# Arm_V2.net
KiCad netlist of a schematic drawn in Altium Designer
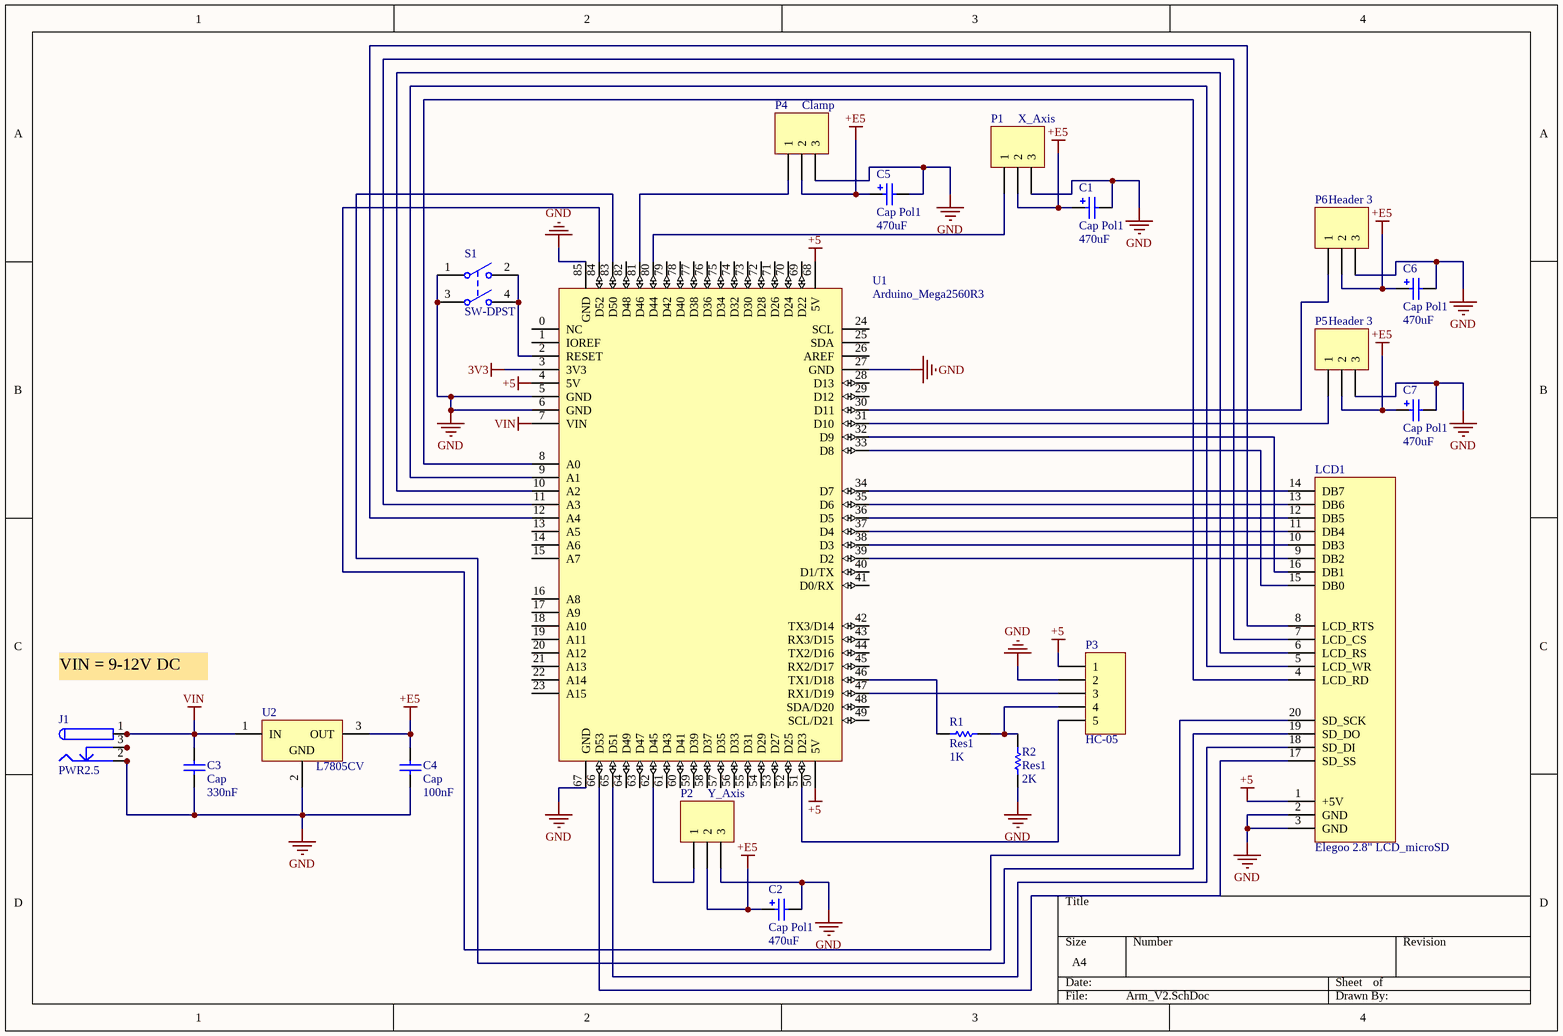
[diagram p0: Arm_V2.SchDoc]

(export (version "E")
  (design (tool "Eeschema 10.0.6"))
  (components
    (comp (ref "C1")
      (value "Cap Pol1")
      (footprint "PCAP_3")
      (description "Polarized Capacitor (Radial)")
      (fields (field (name "ALTIUM_VALUE") "470uF") (field (name "PUBLISHER") "Altium Limited"))
      (libsource (lib "Miscellaneous Devices") (part "Cap Pol1"))
    )
    (comp (ref "C2")
      (value "Cap Pol1")
      (footprint "PCAP_3")
      (description "Polarized Capacitor (Radial)")
      (fields (field (name "ALTIUM_VALUE") "470uF") (field (name "PUBLISHER") "Altium Limited"))
      (libsource (lib "Miscellaneous Devices") (part "Cap Pol1"))
    )
    (comp (ref "C3")
      (value "Cap")
      (footprint "RAD-0.2")
      (description "Capacitor")
      (fields (field (name "ALTIUM_VALUE") "330nF") (field (name "PUBLISHER") "Altium Limited"))
      (libsource (lib "Miscellaneous Devices") (part "Cap"))
    )
    (comp (ref "C4")
      (value "Cap")
      (footprint "RAD-0.2")
      (description "Capacitor")
      (fields (field (name "ALTIUM_VALUE") "100nF") (field (name "PUBLISHER") "Altium Limited"))
      (libsource (lib "Miscellaneous Devices") (part "Cap"))
    )
    (comp (ref "C5")
      (value "Cap Pol1")
      (footprint "PCAP_3")
      (description "Polarized Capacitor (Radial)")
      (fields (field (name "ALTIUM_VALUE") "470uF") (field (name "PUBLISHER") "Altium Limited"))
      (libsource (lib "Miscellaneous Devices") (part "Cap Pol1"))
    )
    (comp (ref "C6")
      (value "Cap Pol1")
      (footprint "PCAP_3")
      (description "Polarized Capacitor (Radial)")
      (fields (field (name "ALTIUM_VALUE") "470uF") (field (name "PUBLISHER") "Altium Limited"))
      (libsource (lib "Miscellaneous Devices") (part "Cap Pol1"))
    )
    (comp (ref "C7")
      (value "Cap Pol1")
      (footprint "PCAP_3")
      (description "Polarized Capacitor (Radial)")
      (fields (field (name "ALTIUM_VALUE") "470uF") (field (name "PUBLISHER") "Altium Limited"))
      (libsource (lib "Miscellaneous Devices") (part "Cap Pol1"))
    )
    (comp (ref "J1")
      (value "PWR2.5")
      (footprint "KLD-0202")
      (description "Low Voltage Power Supply Connector")
      (fields (field (name "PUBLISHER") "Altium Limited"))
      (libsource (lib "Miscellaneous Connectors") (part "PWR2.5"))
    )
    (comp (ref "LCD1")
      (value "Elegoo 2.8\" LCD_microSD")
      (footprint "Elegoo 2.8\" LCD w/h microSD")
      (libsource (lib "Miscellaneous Devices") (part "Elegoo 2.8{dblquote} LCD_microSD"))
    )
    (comp (ref "P1")
      (value "X_Axis")
      (footprint "HDR1X3")
      (description "Header, 3-Pin")
      (fields (field (name "PUBLISHER") "Altium Limited"))
      (libsource (lib "Miscellaneous Connectors") (part "Header 3"))
    )
    (comp (ref "P2")
      (value "Y_Axis")
      (footprint "HDR1X3")
      (description "Header, 3-Pin")
      (fields (field (name "PUBLISHER") "Altium Limited"))
      (libsource (lib "Miscellaneous Connectors") (part "Header 3"))
    )
    (comp (ref "P3")
      (value "HC-05")
      (footprint "HDR1X5H")
      (description "Header, 5-Pin, Right Angle")
      (fields (field (name "PUBLISHER") "Altium Limited"))
      (libsource (lib "Miscellaneous Connectors") (part "Header 5H"))
    )
    (comp (ref "P4")
      (value "Clamp")
      (footprint "HDR1X3")
      (description "Header, 3-Pin")
      (fields (field (name "PUBLISHER") "Altium Limited"))
      (libsource (lib "Miscellaneous Connectors") (part "Header 3"))
    )
    (comp (ref "P5")
      (value "Header 3")
      (footprint "HDR1X3")
      (description "Header, 3-Pin")
      (fields (field (name "PUBLISHER") "Altium Limited"))
      (libsource (lib "Miscellaneous Connectors") (part "Header 3"))
    )
    (comp (ref "P6")
      (value "Header 3")
      (footprint "HDR1X3")
      (description "Header, 3-Pin")
      (fields (field (name "PUBLISHER") "Altium Limited"))
      (libsource (lib "Miscellaneous Connectors") (part "Header 3"))
    )
    (comp (ref "R1")
      (value "Res1")
      (footprint "AXIAL-0.3")
      (description "Resistor")
      (fields (field (name "ALTIUM_VALUE") "1K") (field (name "PUBLISHER") "Altium Limited"))
      (libsource (lib "Miscellaneous Devices") (part "Res1"))
    )
    (comp (ref "R2")
      (value "Res1")
      (footprint "AXIAL-0.3")
      (description "Resistor")
      (fields (field (name "ALTIUM_VALUE") "2K") (field (name "PUBLISHER") "Altium Limited"))
      (libsource (lib "Miscellaneous Devices") (part "Res1"))
    )
    (comp (ref "S1")
      (value "SW-DPST")
      (footprint "DPST-4")
      (description "Double-Pole, Single-Throw Switch")
      (fields (field (name "PUBLISHER") "Altium Limited"))
      (libsource (lib "Miscellaneous Devices") (part "SW-DPST"))
    )
    (comp (ref "U1")
      (value "Arduino_Mega2560R3")
      (footprint "ARDUINO_MEGA2560R3")
      (libsource (lib "Miscellaneous Devices") (part "Arduino_Mega2560R3"))
    )
    (comp (ref "U2")
      (value "L7805CV")
      (footprint "TO220")
      (description "Positive Voltage Regulator, 5V, 3-Pin TO-220")
      (libsource (lib "STMicroelectronics Power Management Linear Regulator") (part "L7805CV"))
    )
  )
  (nets
    (net (code "1") (name "+5") (class "Default")
      (node (ref "LCD1") (pin "1") (pinfunction "+5V_1") (pintype "passive"))
      (node (ref "P3") (pin "1") (pinfunction "1_1") (pintype "passive"))
      (node (ref "U1") (pin "4") (pinfunction "5V_4") (pintype "power_in"))
      (node (ref "U1") (pin "50") (pinfunction "5V_50") (pintype "power_in"))
      (node (ref "U1") (pin "68") (pinfunction "5V_68") (pintype "power_in"))
    )
    (net (code "2") (name "+E5") (class "Default")
      (node (ref "C1") (pin "1") (pinfunction "1_1") (pintype "passive"))
      (node (ref "C2") (pin "1") (pinfunction "1_1") (pintype "passive"))
      (node (ref "C4") (pin "2") (pinfunction "2_2") (pintype "passive"))
      (node (ref "C5") (pin "1") (pinfunction "1_1") (pintype "passive"))
      (node (ref "C6") (pin "1") (pinfunction "1_1") (pintype "passive"))
      (node (ref "C7") (pin "1") (pinfunction "1_1") (pintype "passive"))
      (node (ref "P1") (pin "2") (pinfunction "2_2") (pintype "passive"))
      (node (ref "P2") (pin "2") (pinfunction "2_2") (pintype "passive"))
      (node (ref "P4") (pin "2") (pinfunction "2_2") (pintype "passive"))
      (node (ref "P5") (pin "2") (pinfunction "2_2") (pintype "passive"))
      (node (ref "P6") (pin "2") (pinfunction "2_2") (pintype "passive"))
      (node (ref "U2") (pin "3") (pinfunction "OUT_3") (pintype "power_in"))
    )
    (net (code "3") (name "3V3") (class "Default")
      (node (ref "U1") (pin "3") (pinfunction "3V3_3") (pintype "power_in"))
    )
    (net (code "4") (name "GND") (class "Default")
      (node (ref "C1") (pin "2") (pinfunction "2_2") (pintype "passive"))
      (node (ref "C2") (pin "2") (pinfunction "2_2") (pintype "passive"))
      (node (ref "C3") (pin "1") (pinfunction "1_1") (pintype "passive"))
      (node (ref "C4") (pin "1") (pinfunction "1_1") (pintype "passive"))
      (node (ref "C5") (pin "2") (pinfunction "2_2") (pintype "passive"))
      (node (ref "C6") (pin "2") (pinfunction "2_2") (pintype "passive"))
      (node (ref "C7") (pin "2") (pinfunction "2_2") (pintype "passive"))
      (node (ref "J1") (pin "2") (pinfunction "2_2") (pintype "power_in"))
      (node (ref "J1") (pin "2A") (pinfunction "2A_2A") (pintype "power_in"))
      (node (ref "J1") (pin "2B") (pinfunction "2B_2B") (pintype "power_in"))
      (node (ref "LCD1") (pin "2") (pinfunction "GND_2") (pintype "passive"))
      (node (ref "LCD1") (pin "3") (pinfunction "GND_3") (pintype "passive"))
      (node (ref "P1") (pin "3") (pinfunction "3_3") (pintype "passive"))
      (node (ref "P2") (pin "3") (pinfunction "3_3") (pintype "passive"))
      (node (ref "P3") (pin "2") (pinfunction "2_2") (pintype "passive"))
      (node (ref "P4") (pin "3") (pinfunction "3_3") (pintype "passive"))
      (node (ref "P5") (pin "3") (pinfunction "3_3") (pintype "passive"))
      (node (ref "P6") (pin "3") (pinfunction "3_3") (pintype "passive"))
      (node (ref "R2") (pin "1") (pinfunction "1_1") (pintype "passive"))
      (node (ref "S1") (pin "1") (pinfunction "COMMON1_1") (pintype "passive"))
      (node (ref "S1") (pin "3") (pinfunction "COMMON2_3") (pintype "passive"))
      (node (ref "U1") (pin "27") (pinfunction "GND_27") (pintype "power_in"))
      (node (ref "U1") (pin "5") (pinfunction "GND_5") (pintype "power_in"))
      (node (ref "U1") (pin "6") (pinfunction "GND_6") (pintype "power_in"))
      (node (ref "U1") (pin "67") (pinfunction "GND_67") (pintype "power_in"))
      (node (ref "U1") (pin "85") (pinfunction "GND_85") (pintype "power_in"))
      (node (ref "U2") (pin "2") (pinfunction "GND_2") (pintype "power_in"))
    )
    (net (code "5") (name "Net-(J1-Pad3)") (class "Default")
      (node (ref "J1") (pin "3") (pinfunction "3_3") (pintype "power_in"))
      (node (ref "J1") (pin "3A") (pinfunction "3A_3A") (pintype "power_in"))
      (node (ref "J1") (pin "3B") (pinfunction "3B_3B") (pintype "power_in"))
    )
    (net (code "6") (name "Net-(LCD1-DB0)") (class "Default")
      (node (ref "LCD1") (pin "15") (pinfunction "DB0_15") (pintype "passive"))
      (node (ref "U1") (pin "33") (pinfunction "D8_33") (pintype "bidirectional"))
    )
    (net (code "7") (name "Net-(LCD1-DB1)") (class "Default")
      (node (ref "LCD1") (pin "16") (pinfunction "DB1_16") (pintype "passive"))
      (node (ref "U1") (pin "32") (pinfunction "D9_32") (pintype "bidirectional"))
    )
    (net (code "8") (name "Net-(LCD1-DB2)") (class "Default")
      (node (ref "LCD1") (pin "9") (pinfunction "DB2_9") (pintype "passive"))
      (node (ref "U1") (pin "39") (pinfunction "D2_39") (pintype "bidirectional"))
    )
    (net (code "9") (name "Net-(LCD1-DB3)") (class "Default")
      (node (ref "LCD1") (pin "10") (pinfunction "DB3_10") (pintype "passive"))
      (node (ref "U1") (pin "38") (pinfunction "D3_38") (pintype "bidirectional"))
    )
    (net (code "10") (name "Net-(LCD1-DB4)") (class "Default")
      (node (ref "LCD1") (pin "11") (pinfunction "DB4_11") (pintype "passive"))
      (node (ref "U1") (pin "37") (pinfunction "D4_37") (pintype "bidirectional"))
    )
    (net (code "11") (name "Net-(LCD1-DB5)") (class "Default")
      (node (ref "LCD1") (pin "12") (pinfunction "DB5_12") (pintype "passive"))
      (node (ref "U1") (pin "36") (pinfunction "D5_36") (pintype "bidirectional"))
    )
    (net (code "12") (name "Net-(LCD1-DB6)") (class "Default")
      (node (ref "LCD1") (pin "13") (pinfunction "DB6_13") (pintype "passive"))
      (node (ref "U1") (pin "35") (pinfunction "D6_35") (pintype "bidirectional"))
    )
    (net (code "13") (name "Net-(LCD1-DB7)") (class "Default")
      (node (ref "LCD1") (pin "14") (pinfunction "DB7_14") (pintype "passive"))
      (node (ref "U1") (pin "34") (pinfunction "D7_34") (pintype "bidirectional"))
    )
    (net (code "14") (name "Net-(LCD1-LCD_CS)") (class "Default")
      (node (ref "LCD1") (pin "7") (pinfunction "LCD_CS_7") (pintype "passive"))
      (node (ref "U1") (pin "11") (pinfunction "A3_11") (pintype "passive"))
    )
    (net (code "15") (name "Net-(LCD1-LCD_RD)") (class "Default")
      (node (ref "LCD1") (pin "4") (pinfunction "LCD_RD_4") (pintype "passive"))
      (node (ref "U1") (pin "8") (pinfunction "A0_8") (pintype "passive"))
    )
    (net (code "16") (name "Net-(LCD1-LCD_RS)") (class "Default")
      (node (ref "LCD1") (pin "6") (pinfunction "LCD_RS_6") (pintype "passive"))
      (node (ref "U1") (pin "10") (pinfunction "A2_10") (pintype "passive"))
    )
    (net (code "17") (name "Net-(LCD1-LCD_RTS)") (class "Default")
      (node (ref "LCD1") (pin "8") (pinfunction "LCD_RTS_8") (pintype "passive"))
      (node (ref "U1") (pin "12") (pinfunction "A4_12") (pintype "passive"))
    )
    (net (code "18") (name "Net-(LCD1-LCD_WR)") (class "Default")
      (node (ref "LCD1") (pin "5") (pinfunction "LCD_WR_5") (pintype "passive"))
      (node (ref "U1") (pin "9") (pinfunction "A1_9") (pintype "passive"))
    )
    (net (code "19") (name "Net-(LCD1-SD_DI)") (class "Default")
      (node (ref "LCD1") (pin "18") (pinfunction "SD_DI_18") (pintype "passive"))
      (node (ref "U1") (pin "65") (pinfunction "D51_65") (pintype "bidirectional"))
    )
    (net (code "20") (name "Net-(LCD1-SD_DO)") (class "Default")
      (node (ref "LCD1") (pin "19") (pinfunction "SD_DO_19") (pintype "passive"))
      (node (ref "U1") (pin "83") (pinfunction "D50_83") (pintype "bidirectional"))
    )
    (net (code "21") (name "Net-(LCD1-SD_SCK)") (class "Default")
      (node (ref "LCD1") (pin "20") (pinfunction "SD_SCK_20") (pintype "passive"))
      (node (ref "U1") (pin "84") (pinfunction "D52_84") (pintype "bidirectional"))
    )
    (net (code "22") (name "Net-(LCD1-SD_SS)") (class "Default")
      (node (ref "LCD1") (pin "17") (pinfunction "SD_SS_17") (pintype "passive"))
      (node (ref "U1") (pin "66") (pinfunction "D53_66") (pintype "bidirectional"))
    )
    (net (code "23") (name "Net-(P3-Pad4)") (class "Default")
      (node (ref "P3") (pin "4") (pinfunction "4_4") (pintype "passive"))
      (node (ref "R1") (pin "1") (pinfunction "1_1") (pintype "passive"))
      (node (ref "R2") (pin "2") (pinfunction "2_2") (pintype "passive"))
    )
    (net (code "24") (name "Net-(S1-NO1)") (class "Default")
      (node (ref "S1") (pin "2") (pinfunction "NO1_2") (pintype "passive"))
      (node (ref "S1") (pin "4") (pinfunction "NO2_4") (pintype "passive"))
      (node (ref "U1") (pin "2") (pinfunction "RESET_2") (pintype "passive"))
    )
    (net (code "25") (name "Net-(U1-D10)") (class "Default")
      (node (ref "P5") (pin "1") (pinfunction "1_1") (pintype "passive"))
      (node (ref "U1") (pin "31") (pinfunction "D10_31") (pintype "bidirectional"))
    )
    (net (code "26") (name "Net-(U1-D11)") (class "Default")
      (node (ref "P6") (pin "1") (pinfunction "1_1") (pintype "passive"))
      (node (ref "U1") (pin "30") (pinfunction "D11_30") (pintype "bidirectional"))
    )
    (net (code "27") (name "Net-(U1-D23)") (class "Default")
      (node (ref "P3") (pin "5") (pinfunction "5_5") (pintype "passive"))
      (node (ref "U1") (pin "51") (pinfunction "D23_51") (pintype "bidirectional"))
    )
    (net (code "28") (name "Net-(U1-D44)") (class "Default")
      (node (ref "P1") (pin "1") (pinfunction "1_1") (pintype "passive"))
      (node (ref "U1") (pin "80") (pinfunction "D44_80") (pintype "bidirectional"))
    )
    (net (code "29") (name "Net-(U1-D45)") (class "Default")
      (node (ref "P2") (pin "1") (pinfunction "1_1") (pintype "passive"))
      (node (ref "U1") (pin "62") (pinfunction "D45_62") (pintype "bidirectional"))
    )
    (net (code "30") (name "Net-(U1-D46)") (class "Default")
      (node (ref "P4") (pin "1") (pinfunction "1_1") (pintype "passive"))
      (node (ref "U1") (pin "81") (pinfunction "D46_81") (pintype "bidirectional"))
    )
    (net (code "31") (name "Net-(U1-RX1{slash}D19)") (class "Default")
      (node (ref "P3") (pin "3") (pinfunction "3_3") (pintype "passive"))
      (node (ref "U1") (pin "47") (pinfunction "RX1/D19_47") (pintype "bidirectional"))
    )
    (net (code "32") (name "Net-(U1-TX1{slash}D18)") (class "Default")
      (node (ref "R1") (pin "2") (pinfunction "2_2") (pintype "passive"))
      (node (ref "U1") (pin "46") (pinfunction "TX1/D18_46") (pintype "bidirectional"))
    )
    (net (code "33") (name "VIN") (class "Default")
      (node (ref "C3") (pin "2") (pinfunction "2_2") (pintype "passive"))
      (node (ref "J1") (pin "1") (pinfunction "1_1") (pintype "power_in"))
      (node (ref "J1") (pin "1A") (pinfunction "1A_1A") (pintype "power_in"))
      (node (ref "J1") (pin "1B") (pinfunction "1B_1B") (pintype "power_in"))
      (node (ref "U1") (pin "7") (pinfunction "VIN_7") (pintype "power_in"))
      (node (ref "U2") (pin "1") (pinfunction "IN_1") (pintype "power_in"))
    )
    (net (code "34") (name "unconnected-(U1-A5-Pad13)") (class "Default")
      (node (ref "U1") (pin "13") (pinfunction "A5_13") (pintype "passive"))
    )
    (net (code "35") (name "unconnected-(U1-A6-Pad14)") (class "Default")
      (node (ref "U1") (pin "14") (pinfunction "A6_14") (pintype "passive"))
    )
    (net (code "36") (name "unconnected-(U1-A7-Pad15)") (class "Default")
      (node (ref "U1") (pin "15") (pinfunction "A7_15") (pintype "passive"))
    )
    (net (code "37") (name "unconnected-(U1-A8-Pad16)") (class "Default")
      (node (ref "U1") (pin "16") (pinfunction "A8_16") (pintype "passive"))
    )
    (net (code "38") (name "unconnected-(U1-A9-Pad17)") (class "Default")
      (node (ref "U1") (pin "17") (pinfunction "A9_17") (pintype "passive"))
    )
    (net (code "39") (name "unconnected-(U1-A10-Pad18)") (class "Default")
      (node (ref "U1") (pin "18") (pinfunction "A10_18") (pintype "passive"))
    )
    (net (code "40") (name "unconnected-(U1-A11-Pad19)") (class "Default")
      (node (ref "U1") (pin "19") (pinfunction "A11_19") (pintype "passive"))
    )
    (net (code "41") (name "unconnected-(U1-A12-Pad20)") (class "Default")
      (node (ref "U1") (pin "20") (pinfunction "A12_20") (pintype "passive"))
    )
    (net (code "42") (name "unconnected-(U1-A13-Pad21)") (class "Default")
      (node (ref "U1") (pin "21") (pinfunction "A13_21") (pintype "passive"))
    )
    (net (code "43") (name "unconnected-(U1-A14-Pad22)") (class "Default")
      (node (ref "U1") (pin "22") (pinfunction "A14_22") (pintype "passive"))
    )
    (net (code "44") (name "unconnected-(U1-A15-Pad23)") (class "Default")
      (node (ref "U1") (pin "23") (pinfunction "A15_23") (pintype "passive"))
    )
    (net (code "45") (name "unconnected-(U1-AREF-Pad26)") (class "Default")
      (node (ref "U1") (pin "26") (pinfunction "AREF_26") (pintype "passive"))
    )
    (net (code "46") (name "unconnected-(U1-D0{slash}RX-Pad41)") (class "Default")
      (node (ref "U1") (pin "41") (pinfunction "D0/RX_41") (pintype "bidirectional"))
    )
    (net (code "47") (name "unconnected-(U1-D1{slash}TX-Pad40)") (class "Default")
      (node (ref "U1") (pin "40") (pinfunction "D1/TX_40") (pintype "bidirectional"))
    )
    (net (code "48") (name "unconnected-(U1-D12-Pad29)") (class "Default")
      (node (ref "U1") (pin "29") (pinfunction "D12_29") (pintype "bidirectional"))
    )
    (net (code "49") (name "unconnected-(U1-D13-Pad28)") (class "Default")
      (node (ref "U1") (pin "28") (pinfunction "D13_28") (pintype "bidirectional"))
    )
    (net (code "50") (name "unconnected-(U1-D22-Pad69)") (class "Default")
      (node (ref "U1") (pin "69") (pinfunction "D22_69") (pintype "bidirectional"))
    )
    (net (code "51") (name "unconnected-(U1-D24-Pad70)") (class "Default")
      (node (ref "U1") (pin "70") (pinfunction "D24_70") (pintype "bidirectional"))
    )
    (net (code "52") (name "unconnected-(U1-D25-Pad52)") (class "Default")
      (node (ref "U1") (pin "52") (pinfunction "D25_52") (pintype "bidirectional"))
    )
    (net (code "53") (name "unconnected-(U1-D26-Pad71)") (class "Default")
      (node (ref "U1") (pin "71") (pinfunction "D26_71") (pintype "bidirectional"))
    )
    (net (code "54") (name "unconnected-(U1-D27-Pad53)") (class "Default")
      (node (ref "U1") (pin "53") (pinfunction "D27_53") (pintype "bidirectional"))
    )
    (net (code "55") (name "unconnected-(U1-D28-Pad72)") (class "Default")
      (node (ref "U1") (pin "72") (pinfunction "D28_72") (pintype "bidirectional"))
    )
    (net (code "56") (name "unconnected-(U1-D29-Pad54)") (class "Default")
      (node (ref "U1") (pin "54") (pinfunction "D29_54") (pintype "bidirectional"))
    )
    (net (code "57") (name "unconnected-(U1-D30-Pad73)") (class "Default")
      (node (ref "U1") (pin "73") (pinfunction "D30_73") (pintype "bidirectional"))
    )
    (net (code "58") (name "unconnected-(U1-D31-Pad55)") (class "Default")
      (node (ref "U1") (pin "55") (pinfunction "D31_55") (pintype "bidirectional"))
    )
    (net (code "59") (name "unconnected-(U1-D32-Pad74)") (class "Default")
      (node (ref "U1") (pin "74") (pinfunction "D32_74") (pintype "bidirectional"))
    )
    (net (code "60") (name "unconnected-(U1-D33-Pad56)") (class "Default")
      (node (ref "U1") (pin "56") (pinfunction "D33_56") (pintype "bidirectional"))
    )
    (net (code "61") (name "unconnected-(U1-D34-Pad75)") (class "Default")
      (node (ref "U1") (pin "75") (pinfunction "D34_75") (pintype "bidirectional"))
    )
    (net (code "62") (name "unconnected-(U1-D35-Pad57)") (class "Default")
      (node (ref "U1") (pin "57") (pinfunction "D35_57") (pintype "bidirectional"))
    )
    (net (code "63") (name "unconnected-(U1-D36-Pad76)") (class "Default")
      (node (ref "U1") (pin "76") (pinfunction "D36_76") (pintype "bidirectional"))
    )
    (net (code "64") (name "unconnected-(U1-D37-Pad58)") (class "Default")
      (node (ref "U1") (pin "58") (pinfunction "D37_58") (pintype "bidirectional"))
    )
    (net (code "65") (name "unconnected-(U1-D38-Pad77)") (class "Default")
      (node (ref "U1") (pin "77") (pinfunction "D38_77") (pintype "bidirectional"))
    )
    (net (code "66") (name "unconnected-(U1-D39-Pad59)") (class "Default")
      (node (ref "U1") (pin "59") (pinfunction "D39_59") (pintype "bidirectional"))
    )
    (net (code "67") (name "unconnected-(U1-D40-Pad78)") (class "Default")
      (node (ref "U1") (pin "78") (pinfunction "D40_78") (pintype "bidirectional"))
    )
    (net (code "68") (name "unconnected-(U1-D41-Pad60)") (class "Default")
      (node (ref "U1") (pin "60") (pinfunction "D41_60") (pintype "bidirectional"))
    )
    (net (code "69") (name "unconnected-(U1-D42-Pad79)") (class "Default")
      (node (ref "U1") (pin "79") (pinfunction "D42_79") (pintype "bidirectional"))
    )
    (net (code "70") (name "unconnected-(U1-D43-Pad61)") (class "Default")
      (node (ref "U1") (pin "61") (pinfunction "D43_61") (pintype "bidirectional"))
    )
    (net (code "71") (name "unconnected-(U1-D47-Pad63)") (class "Default")
      (node (ref "U1") (pin "63") (pinfunction "D47_63") (pintype "bidirectional"))
    )
    (net (code "72") (name "unconnected-(U1-D48-Pad82)") (class "Default")
      (node (ref "U1") (pin "82") (pinfunction "D48_82") (pintype "bidirectional"))
    )
    (net (code "73") (name "unconnected-(U1-D49-Pad64)") (class "Default")
      (node (ref "U1") (pin "64") (pinfunction "D49_64") (pintype "bidirectional"))
    )
    (net (code "74") (name "unconnected-(U1-IOREF-Pad1)") (class "Default")
      (node (ref "U1") (pin "1") (pinfunction "IOREF_1") (pintype "passive"))
    )
    (net (code "75") (name "unconnected-(U1-NC-Pad0)") (class "Default")
      (node (ref "U1") (pin "0") (pinfunction "NC_0") (pintype "passive"))
    )
    (net (code "76") (name "unconnected-(U1-RX2{slash}D17-Pad45)") (class "Default")
      (node (ref "U1") (pin "45") (pinfunction "RX2/D17_45") (pintype "bidirectional"))
    )
    (net (code "77") (name "unconnected-(U1-RX3{slash}D15-Pad43)") (class "Default")
      (node (ref "U1") (pin "43") (pinfunction "RX3/D15_43") (pintype "bidirectional"))
    )
    (net (code "78") (name "unconnected-(U1-SCL-Pad24)") (class "Default")
      (node (ref "U1") (pin "24") (pinfunction "SCL_24") (pintype "passive"))
    )
    (net (code "79") (name "unconnected-(U1-SCL{slash}D21-Pad49)") (class "Default")
      (node (ref "U1") (pin "49") (pinfunction "SCL/D21_49") (pintype "bidirectional"))
    )
    (net (code "80") (name "unconnected-(U1-SDA-Pad25)") (class "Default")
      (node (ref "U1") (pin "25") (pinfunction "SDA_25") (pintype "passive"))
    )
    (net (code "81") (name "unconnected-(U1-SDA{slash}D20-Pad48)") (class "Default")
      (node (ref "U1") (pin "48") (pinfunction "SDA/D20_48") (pintype "bidirectional"))
    )
    (net (code "82") (name "unconnected-(U1-TX2{slash}D16-Pad44)") (class "Default")
      (node (ref "U1") (pin "44") (pinfunction "TX2/D16_44") (pintype "bidirectional"))
    )
    (net (code "83") (name "unconnected-(U1-TX3{slash}D14-Pad42)") (class "Default")
      (node (ref "U1") (pin "42") (pinfunction "TX3/D14_42") (pintype "bidirectional"))
    )
  )
)
